# fpga_ram_V1.net
KiCad netlist of a schematic drawn in Altium Designer
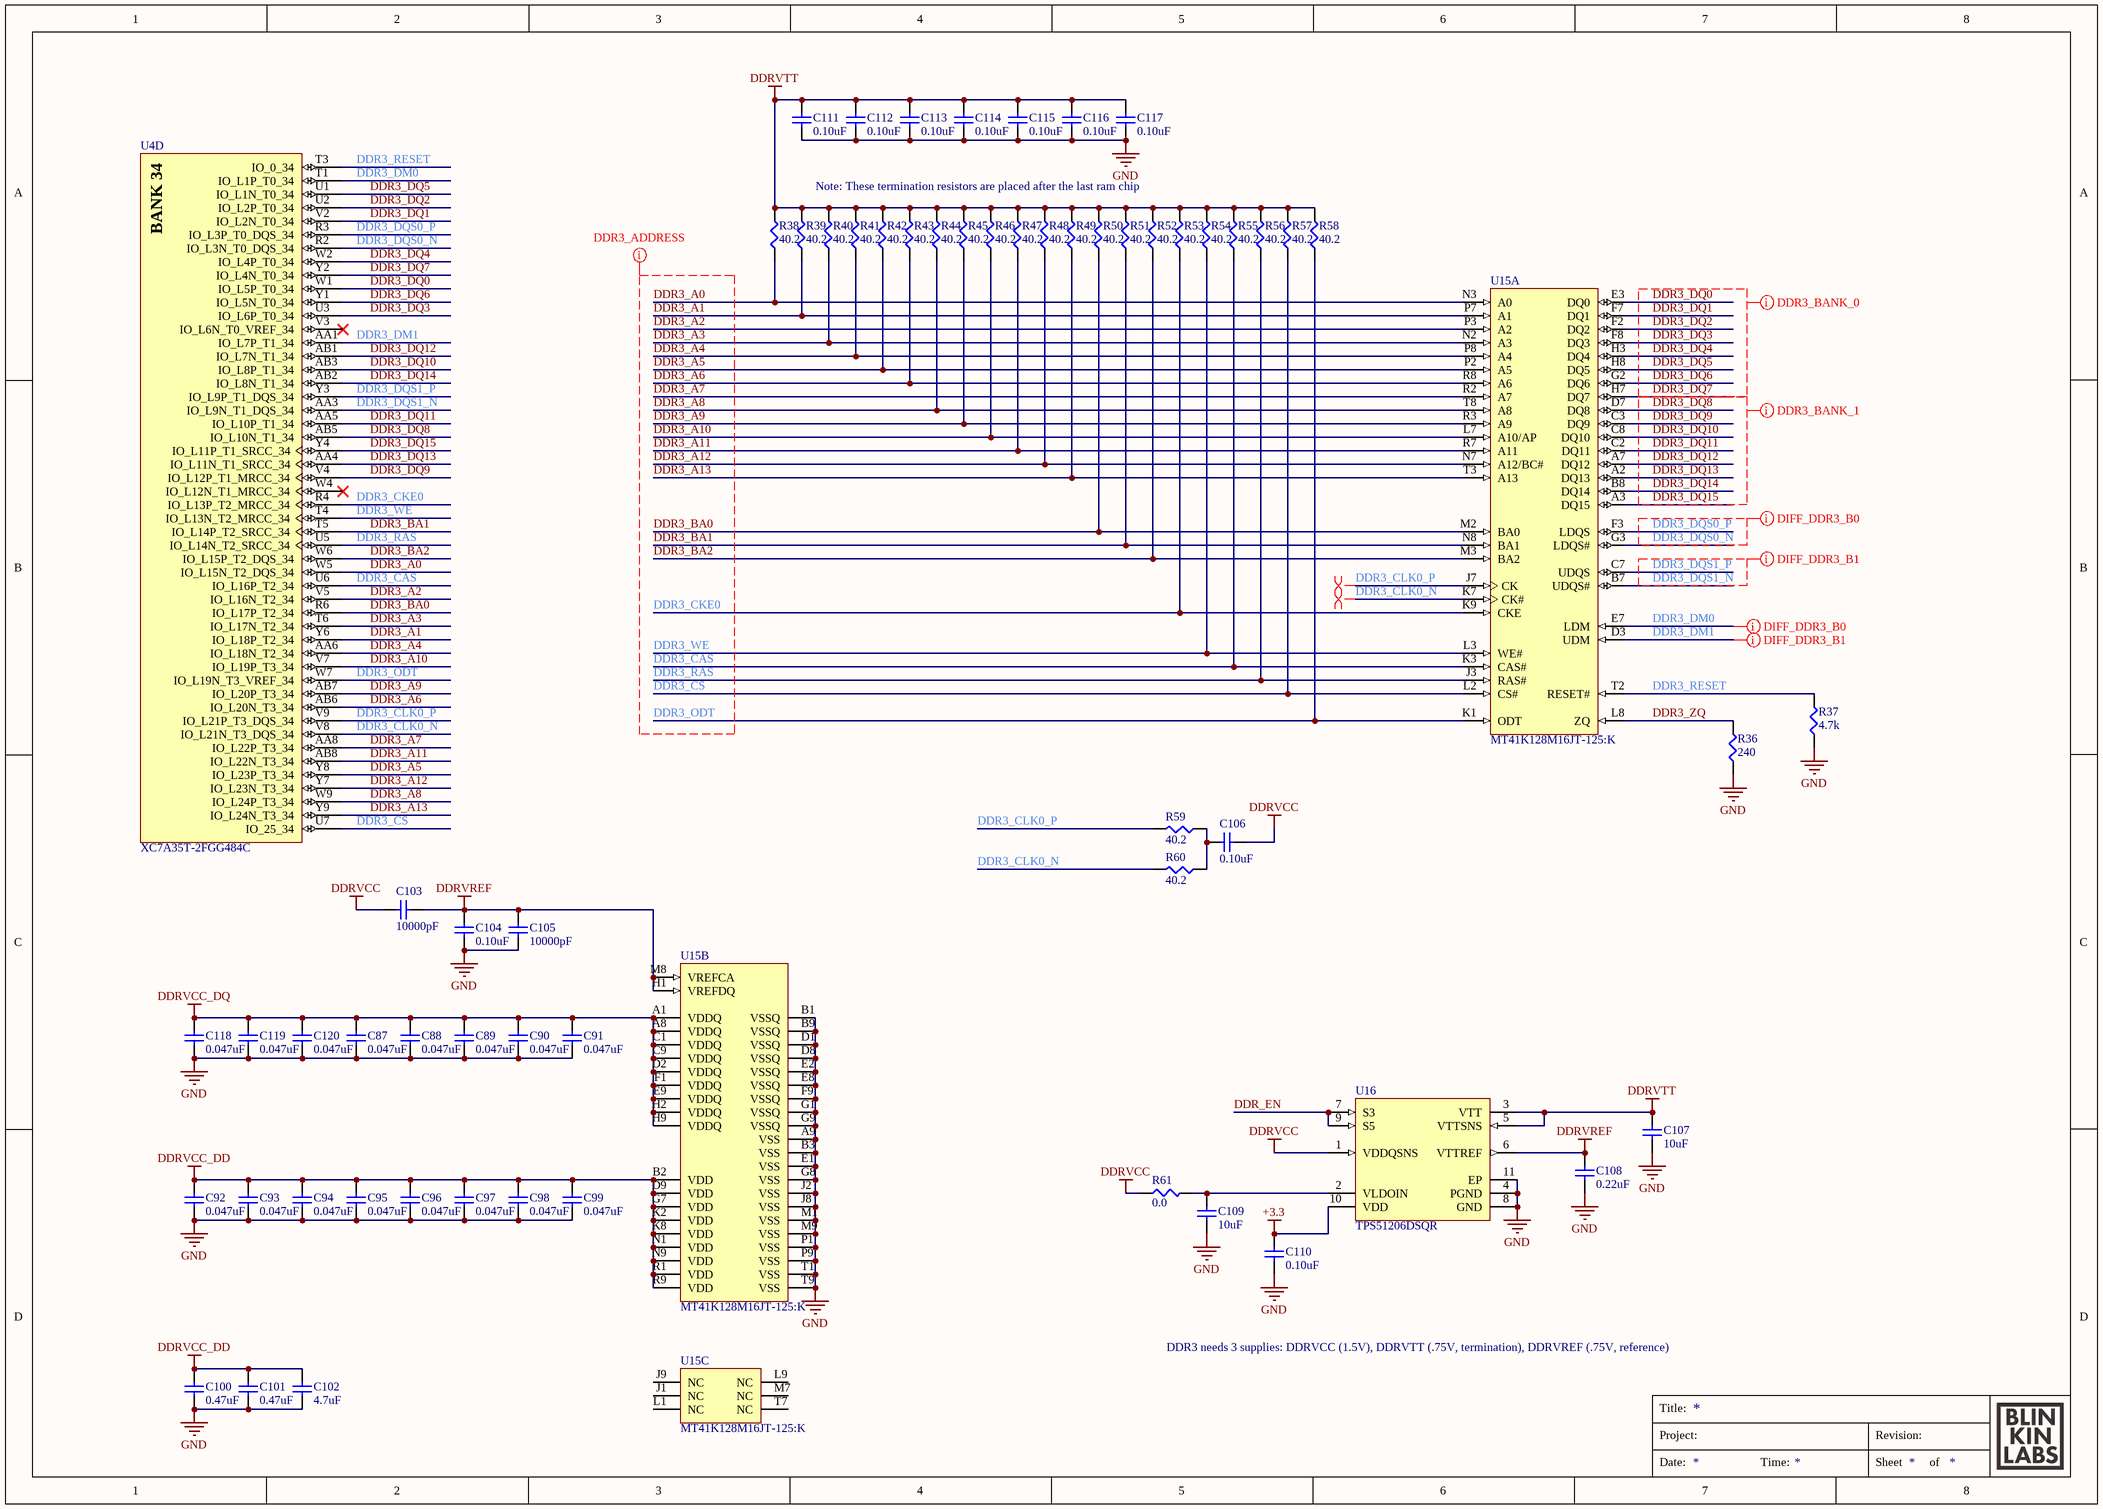
[diagram p0: fpga ram V1.SchDoc]

(export (version "E")
  (design (tool "Eeschema 10.0.6"))
  (components
    (comp (ref "C87")
      (value "0.047uF")
      (footprint "CAPC1005X06L")
      (description "CAP CER 0.047UF 6.3V X5R 0402")
      (fields
        (field (name "PARTNUMBER") "GRM155R60J473KA01D")
        (field (name "DIGI-KEY PART NUMBER") "490-8250-1-ND")
      )
      (libsource (lib "cap_murata") (part "CAPACITOR"))
    )
    (comp (ref "C88")
      (value "0.047uF")
      (footprint "CAPC1005X06L")
      (description "CAP CER 0.047UF 6.3V X5R 0402")
      (fields
        (field (name "PARTNUMBER") "GRM155R60J473KA01D")
        (field (name "DIGI-KEY PART NUMBER") "490-8250-1-ND")
      )
      (libsource (lib "cap_murata") (part "CAPACITOR"))
    )
    (comp (ref "C89")
      (value "0.047uF")
      (footprint "CAPC1005X06L")
      (description "CAP CER 0.047UF 6.3V X5R 0402")
      (fields
        (field (name "PARTNUMBER") "GRM155R60J473KA01D")
        (field (name "DIGI-KEY PART NUMBER") "490-8250-1-ND")
      )
      (libsource (lib "cap_murata") (part "CAPACITOR"))
    )
    (comp (ref "C90")
      (value "0.047uF")
      (footprint "CAPC1005X06L")
      (description "CAP CER 0.047UF 6.3V X5R 0402")
      (fields
        (field (name "PARTNUMBER") "GRM155R60J473KA01D")
        (field (name "DIGI-KEY PART NUMBER") "490-8250-1-ND")
      )
      (libsource (lib "cap_murata") (part "CAPACITOR"))
    )
    (comp (ref "C91")
      (value "0.047uF")
      (footprint "CAPC1005X06L")
      (description "CAP CER 0.047UF 6.3V X5R 0402")
      (fields
        (field (name "PARTNUMBER") "GRM155R60J473KA01D")
        (field (name "DIGI-KEY PART NUMBER") "490-8250-1-ND")
      )
      (libsource (lib "cap_murata") (part "CAPACITOR"))
    )
    (comp (ref "C92")
      (value "0.047uF")
      (footprint "CAPC1005X06L")
      (description "CAP CER 0.047UF 6.3V X5R 0402")
      (fields
        (field (name "PARTNUMBER") "GRM155R60J473KA01D")
        (field (name "DIGI-KEY PART NUMBER") "490-8250-1-ND")
      )
      (libsource (lib "cap_murata") (part "CAPACITOR"))
    )
    (comp (ref "C93")
      (value "0.047uF")
      (footprint "CAPC1005X06L")
      (description "CAP CER 0.047UF 6.3V X5R 0402")
      (fields
        (field (name "PARTNUMBER") "GRM155R60J473KA01D")
        (field (name "DIGI-KEY PART NUMBER") "490-8250-1-ND")
      )
      (libsource (lib "cap_murata") (part "CAPACITOR"))
    )
    (comp (ref "C94")
      (value "0.047uF")
      (footprint "CAPC1005X06L")
      (description "CAP CER 0.047UF 6.3V X5R 0402")
      (fields
        (field (name "PARTNUMBER") "GRM155R60J473KA01D")
        (field (name "DIGI-KEY PART NUMBER") "490-8250-1-ND")
      )
      (libsource (lib "cap_murata") (part "CAPACITOR"))
    )
    (comp (ref "C95")
      (value "0.047uF")
      (footprint "CAPC1005X06L")
      (description "CAP CER 0.047UF 6.3V X5R 0402")
      (fields
        (field (name "PARTNUMBER") "GRM155R60J473KA01D")
        (field (name "DIGI-KEY PART NUMBER") "490-8250-1-ND")
      )
      (libsource (lib "cap_murata") (part "CAPACITOR"))
    )
    (comp (ref "C96")
      (value "0.047uF")
      (footprint "CAPC1005X06L")
      (description "CAP CER 0.047UF 6.3V X5R 0402")
      (fields
        (field (name "PARTNUMBER") "GRM155R60J473KA01D")
        (field (name "DIGI-KEY PART NUMBER") "490-8250-1-ND")
      )
      (libsource (lib "cap_murata") (part "CAPACITOR"))
    )
    (comp (ref "C97")
      (value "0.047uF")
      (footprint "CAPC1005X06L")
      (description "CAP CER 0.047UF 6.3V X5R 0402")
      (fields
        (field (name "PARTNUMBER") "GRM155R60J473KA01D")
        (field (name "DIGI-KEY PART NUMBER") "490-8250-1-ND")
      )
      (libsource (lib "cap_murata") (part "CAPACITOR"))
    )
    (comp (ref "C98")
      (value "0.047uF")
      (footprint "CAPC1005X06L")
      (description "CAP CER 0.047UF 6.3V X5R 0402")
      (fields
        (field (name "PARTNUMBER") "GRM155R60J473KA01D")
        (field (name "DIGI-KEY PART NUMBER") "490-8250-1-ND")
      )
      (libsource (lib "cap_murata") (part "CAPACITOR"))
    )
    (comp (ref "C99")
      (value "0.047uF")
      (footprint "CAPC1005X06L")
      (description "CAP CER 0.047UF 6.3V X5R 0402")
      (fields
        (field (name "PARTNUMBER") "GRM155R60J473KA01D")
        (field (name "DIGI-KEY PART NUMBER") "490-8250-1-ND")
      )
      (libsource (lib "cap_murata") (part "CAPACITOR"))
    )
    (comp (ref "C100")
      (value "0.47uF")
      (footprint "CAPC1005X06L")
      (description "CAP CER 0.47UF 6.3V X5R 0402")
      (fields
        (field (name "PARTNUMBER") "GRM155R60J474KE19D")
        (field (name "DIGI-KEY PART NUMBER") "490-3266-1-ND")
      )
      (libsource (lib "cap_murata") (part "CAPACITOR"))
    )
    (comp (ref "C101")
      (value "0.47uF")
      (footprint "CAPC1005X06L")
      (description "CAP CER 0.47UF 6.3V X5R 0402")
      (fields
        (field (name "PARTNUMBER") "GRM155R60J474KE19D")
        (field (name "DIGI-KEY PART NUMBER") "490-3266-1-ND")
      )
      (libsource (lib "cap_murata") (part "CAPACITOR"))
    )
    (comp (ref "C102")
      (value "4.7uF")
      (footprint "CAPC1005X06L")
      (description "CAP CER 4.7UF 4V X5R 0402")
      (fields
        (field (name "PARTNUMBER") "GRM155R60G475ME47D")
        (field (name "DIGI-KEY PART NUMBER") "490-11980-1-ND")
      )
      (libsource (lib "cap_murata") (part "CAPACITOR"))
    )
    (comp (ref "C103")
      (value "10000pF")
      (footprint "CAPC1005X06L")
      (description "CAP CER 10000PF 16V X7R 0402")
      (fields
        (field (name "PARTNUMBER") "GRM155R71C103KA01D")
        (field (name "DIGI-KEY PART NUMBER") "490-1313-1-ND")
      )
      (libsource (lib "cap_murata") (part "CAPACITOR"))
    )
    (comp (ref "C104")
      (value "0.10uF")
      (footprint "CAPC1005X06L")
      (description "CAP CER 0.1UF 10V X5R 0402")
      (fields
        (field (name "PARTNUMBER") "GRM155R61A104KA01D")
        (field (name "DIGI-KEY PART NUMBER") "490-1318-1-ND")
      )
      (libsource (lib "cap_murata") (part "CAPACITOR"))
    )
    (comp (ref "C105")
      (value "10000pF")
      (footprint "CAPC1005X06L")
      (description "CAP CER 10000PF 16V X7R 0402")
      (fields
        (field (name "PARTNUMBER") "GRM155R71C103KA01D")
        (field (name "DIGI-KEY PART NUMBER") "490-1313-1-ND")
      )
      (libsource (lib "cap_murata") (part "CAPACITOR"))
    )
    (comp (ref "C106")
      (value "0.10uF")
      (footprint "CAPC1005X06L")
      (description "CAP CER 0.1UF 10V X5R 0402")
      (fields
        (field (name "PARTNUMBER") "GRM155R61A104KA01D")
        (field (name "DIGI-KEY PART NUMBER") "490-1318-1-ND")
      )
      (libsource (lib "cap_murata") (part "CAPACITOR"))
    )
    (comp (ref "C107")
      (value "10uF")
      (footprint "CAPC1608X09L")
      (description "CAP CER 10UF 6.3V X5R 0603")
      (fields
        (field (name "PARTNUMBER") "GRM188R60J106ME47D")
        (field (name "DIGI-KEY PART NUMBER") "490-3896-1-ND")
      )
      (libsource (lib "cap_murata") (part "CAPACITOR"))
    )
    (comp (ref "C108")
      (value "0.22uF")
      (footprint "CAPC1005X06L")
      (description "CAP CER 0.22UF 10V X5R 0402")
      (fields
        (field (name "PARTNUMBER") "GRM155R61A224KE19J")
        (field (name "DIGI-KEY PART NUMBER") "490-6303-1-ND")
      )
      (libsource (lib "cap_murata") (part "CAPACITOR"))
    )
    (comp (ref "C109")
      (value "10uF")
      (footprint "CAPC1608X09L")
      (description "CAP CER 10UF 6.3V X5R 0603")
      (fields
        (field (name "PARTNUMBER") "GRM188R60J106ME47D")
        (field (name "DIGI-KEY PART NUMBER") "490-3896-1-ND")
      )
      (libsource (lib "cap_murata") (part "CAPACITOR"))
    )
    (comp (ref "C110")
      (value "0.10uF")
      (footprint "CAPC1005X06L")
      (description "CAP CER 0.1UF 10V X5R 0402")
      (fields
        (field (name "PARTNUMBER") "GRM155R61A104KA01D")
        (field (name "DIGI-KEY PART NUMBER") "490-1318-1-ND")
      )
      (libsource (lib "cap_murata") (part "CAPACITOR"))
    )
    (comp (ref "C111")
      (value "0.10uF")
      (footprint "CAPC1005X06L")
      (description "CAP CER 0.1UF 10V X5R 0402")
      (fields
        (field (name "PARTNUMBER") "GRM155R61A104KA01D")
        (field (name "DIGI-KEY PART NUMBER") "490-1318-1-ND")
      )
      (libsource (lib "cap_murata") (part "CAPACITOR"))
    )
    (comp (ref "C112")
      (value "0.10uF")
      (footprint "CAPC1005X06L")
      (description "CAP CER 0.1UF 10V X5R 0402")
      (fields
        (field (name "PARTNUMBER") "GRM155R61A104KA01D")
        (field (name "DIGI-KEY PART NUMBER") "490-1318-1-ND")
      )
      (libsource (lib "cap_murata") (part "CAPACITOR"))
    )
    (comp (ref "C113")
      (value "0.10uF")
      (footprint "CAPC1005X06L")
      (description "CAP CER 0.1UF 10V X5R 0402")
      (fields
        (field (name "PARTNUMBER") "GRM155R61A104KA01D")
        (field (name "DIGI-KEY PART NUMBER") "490-1318-1-ND")
      )
      (libsource (lib "cap_murata") (part "CAPACITOR"))
    )
    (comp (ref "C114")
      (value "0.10uF")
      (footprint "CAPC1005X06L")
      (description "CAP CER 0.1UF 10V X5R 0402")
      (fields
        (field (name "PARTNUMBER") "GRM155R61A104KA01D")
        (field (name "DIGI-KEY PART NUMBER") "490-1318-1-ND")
      )
      (libsource (lib "cap_murata") (part "CAPACITOR"))
    )
    (comp (ref "C115")
      (value "0.10uF")
      (footprint "CAPC1005X06L")
      (description "CAP CER 0.1UF 10V X5R 0402")
      (fields
        (field (name "PARTNUMBER") "GRM155R61A104KA01D")
        (field (name "DIGI-KEY PART NUMBER") "490-1318-1-ND")
      )
      (libsource (lib "cap_murata") (part "CAPACITOR"))
    )
    (comp (ref "C116")
      (value "0.10uF")
      (footprint "CAPC1005X06L")
      (description "CAP CER 0.1UF 10V X5R 0402")
      (fields
        (field (name "PARTNUMBER") "GRM155R61A104KA01D")
        (field (name "DIGI-KEY PART NUMBER") "490-1318-1-ND")
      )
      (libsource (lib "cap_murata") (part "CAPACITOR"))
    )
    (comp (ref "C117")
      (value "0.10uF")
      (footprint "CAPC1005X06L")
      (description "CAP CER 0.1UF 10V X5R 0402")
      (fields
        (field (name "PARTNUMBER") "GRM155R61A104KA01D")
        (field (name "DIGI-KEY PART NUMBER") "490-1318-1-ND")
      )
      (libsource (lib "cap_murata") (part "CAPACITOR"))
    )
    (comp (ref "C118")
      (value "0.047uF")
      (footprint "CAPC1005X06L")
      (description "CAP CER 0.047UF 6.3V X5R 0402")
      (fields
        (field (name "PARTNUMBER") "GRM155R60J473KA01D")
        (field (name "DIGI-KEY PART NUMBER") "490-8250-1-ND")
      )
      (libsource (lib "cap_murata") (part "CAPACITOR"))
    )
    (comp (ref "C119")
      (value "0.047uF")
      (footprint "CAPC1005X06L")
      (description "CAP CER 0.047UF 6.3V X5R 0402")
      (fields
        (field (name "PARTNUMBER") "GRM155R60J473KA01D")
        (field (name "DIGI-KEY PART NUMBER") "490-8250-1-ND")
      )
      (libsource (lib "cap_murata") (part "CAPACITOR"))
    )
    (comp (ref "C120")
      (value "0.047uF")
      (footprint "CAPC1005X06L")
      (description "CAP CER 0.047UF 6.3V X5R 0402")
      (fields
        (field (name "PARTNUMBER") "GRM155R60J473KA01D")
        (field (name "DIGI-KEY PART NUMBER") "490-8250-1-ND")
      )
      (libsource (lib "cap_murata") (part "CAPACITOR"))
    )
    (comp (ref "R36")
      (value "240")
      (footprint "ERJ2G(0402)_L")
      (description "RES SMD 240 OHM 1% 1/10W 0402")
      (fields (field (name "PARTNUMBER") "ERJ-2RKF2400X") (field (name "DIGI-KEY PART NUMBER") "P240LCT-ND"))
      (libsource (lib "res_panasonic_erj_xls") (part "RESISTOR"))
    )
    (comp (ref "R37")
      (value "4.7k")
      (footprint "ERJ2G(0402)_L")
      (description "RES SMD 4.7K OHM 1% 1/5W 0402")
      (fields (field (name "PARTNUMBER") "ERJ-PA2F4701X") (field (name "DIGI-KEY PART NUMBER") "P17228CT-ND"))
      (libsource (lib "res_panasonic_erj_xls") (part "RESISTOR"))
    )
    (comp (ref "R38")
      (value "40.2")
      (footprint "ERJ2G(0402)_L")
      (description "RES SMD 40.2 OHM 1% 1/10W 0402")
      (fields (field (name "PARTNUMBER") "ERJ-2RKF40R2X") (field (name "DIGI-KEY PART NUMBER") "P40.2LCT-ND"))
      (libsource (lib "res_panasonic_erj_xls") (part "RESISTOR"))
    )
    (comp (ref "R39")
      (value "40.2")
      (footprint "ERJ2G(0402)_L")
      (description "RES SMD 40.2 OHM 1% 1/10W 0402")
      (fields (field (name "PARTNUMBER") "ERJ-2RKF40R2X") (field (name "DIGI-KEY PART NUMBER") "P40.2LCT-ND"))
      (libsource (lib "res_panasonic_erj_xls") (part "RESISTOR"))
    )
    (comp (ref "R40")
      (value "40.2")
      (footprint "ERJ2G(0402)_L")
      (description "RES SMD 40.2 OHM 1% 1/10W 0402")
      (fields (field (name "PARTNUMBER") "ERJ-2RKF40R2X") (field (name "DIGI-KEY PART NUMBER") "P40.2LCT-ND"))
      (libsource (lib "res_panasonic_erj_xls") (part "RESISTOR"))
    )
    (comp (ref "R41")
      (value "40.2")
      (footprint "ERJ2G(0402)_L")
      (description "RES SMD 40.2 OHM 1% 1/10W 0402")
      (fields (field (name "PARTNUMBER") "ERJ-2RKF40R2X") (field (name "DIGI-KEY PART NUMBER") "P40.2LCT-ND"))
      (libsource (lib "res_panasonic_erj_xls") (part "RESISTOR"))
    )
    (comp (ref "R42")
      (value "40.2")
      (footprint "ERJ2G(0402)_L")
      (description "RES SMD 40.2 OHM 1% 1/10W 0402")
      (fields (field (name "PARTNUMBER") "ERJ-2RKF40R2X") (field (name "DIGI-KEY PART NUMBER") "P40.2LCT-ND"))
      (libsource (lib "res_panasonic_erj_xls") (part "RESISTOR"))
    )
    (comp (ref "R43")
      (value "40.2")
      (footprint "ERJ2G(0402)_L")
      (description "RES SMD 40.2 OHM 1% 1/10W 0402")
      (fields (field (name "PARTNUMBER") "ERJ-2RKF40R2X") (field (name "DIGI-KEY PART NUMBER") "P40.2LCT-ND"))
      (libsource (lib "res_panasonic_erj_xls") (part "RESISTOR"))
    )
    (comp (ref "R44")
      (value "40.2")
      (footprint "ERJ2G(0402)_L")
      (description "RES SMD 40.2 OHM 1% 1/10W 0402")
      (fields (field (name "PARTNUMBER") "ERJ-2RKF40R2X") (field (name "DIGI-KEY PART NUMBER") "P40.2LCT-ND"))
      (libsource (lib "res_panasonic_erj_xls") (part "RESISTOR"))
    )
    (comp (ref "R45")
      (value "40.2")
      (footprint "ERJ2G(0402)_L")
      (description "RES SMD 40.2 OHM 1% 1/10W 0402")
      (fields (field (name "PARTNUMBER") "ERJ-2RKF40R2X") (field (name "DIGI-KEY PART NUMBER") "P40.2LCT-ND"))
      (libsource (lib "res_panasonic_erj_xls") (part "RESISTOR"))
    )
    (comp (ref "R46")
      (value "40.2")
      (footprint "ERJ2G(0402)_L")
      (description "RES SMD 40.2 OHM 1% 1/10W 0402")
      (fields (field (name "PARTNUMBER") "ERJ-2RKF40R2X") (field (name "DIGI-KEY PART NUMBER") "P40.2LCT-ND"))
      (libsource (lib "res_panasonic_erj_xls") (part "RESISTOR"))
    )
    (comp (ref "R47")
      (value "40.2")
      (footprint "ERJ2G(0402)_L")
      (description "RES SMD 40.2 OHM 1% 1/10W 0402")
      (fields (field (name "PARTNUMBER") "ERJ-2RKF40R2X") (field (name "DIGI-KEY PART NUMBER") "P40.2LCT-ND"))
      (libsource (lib "res_panasonic_erj_xls") (part "RESISTOR"))
    )
    (comp (ref "R48")
      (value "40.2")
      (footprint "ERJ2G(0402)_L")
      (description "RES SMD 40.2 OHM 1% 1/10W 0402")
      (fields (field (name "PARTNUMBER") "ERJ-2RKF40R2X") (field (name "DIGI-KEY PART NUMBER") "P40.2LCT-ND"))
      (libsource (lib "res_panasonic_erj_xls") (part "RESISTOR"))
    )
    (comp (ref "R49")
      (value "40.2")
      (footprint "ERJ2G(0402)_L")
      (description "RES SMD 40.2 OHM 1% 1/10W 0402")
      (fields (field (name "PARTNUMBER") "ERJ-2RKF40R2X") (field (name "DIGI-KEY PART NUMBER") "P40.2LCT-ND"))
      (libsource (lib "res_panasonic_erj_xls") (part "RESISTOR"))
    )
    (comp (ref "R50")
      (value "40.2")
      (footprint "ERJ2G(0402)_L")
      (description "RES SMD 40.2 OHM 1% 1/10W 0402")
      (fields (field (name "PARTNUMBER") "ERJ-2RKF40R2X") (field (name "DIGI-KEY PART NUMBER") "P40.2LCT-ND"))
      (libsource (lib "res_panasonic_erj_xls") (part "RESISTOR"))
    )
    (comp (ref "R51")
      (value "40.2")
      (footprint "ERJ2G(0402)_L")
      (description "RES SMD 40.2 OHM 1% 1/10W 0402")
      (fields (field (name "PARTNUMBER") "ERJ-2RKF40R2X") (field (name "DIGI-KEY PART NUMBER") "P40.2LCT-ND"))
      (libsource (lib "res_panasonic_erj_xls") (part "RESISTOR"))
    )
    (comp (ref "R52")
      (value "40.2")
      (footprint "ERJ2G(0402)_L")
      (description "RES SMD 40.2 OHM 1% 1/10W 0402")
      (fields (field (name "PARTNUMBER") "ERJ-2RKF40R2X") (field (name "DIGI-KEY PART NUMBER") "P40.2LCT-ND"))
      (libsource (lib "res_panasonic_erj_xls") (part "RESISTOR"))
    )
    (comp (ref "R53")
      (value "40.2")
      (footprint "ERJ2G(0402)_L")
      (description "RES SMD 40.2 OHM 1% 1/10W 0402")
      (fields (field (name "PARTNUMBER") "ERJ-2RKF40R2X") (field (name "DIGI-KEY PART NUMBER") "P40.2LCT-ND"))
      (libsource (lib "res_panasonic_erj_xls") (part "RESISTOR"))
    )
    (comp (ref "R54")
      (value "40.2")
      (footprint "ERJ2G(0402)_L")
      (description "RES SMD 40.2 OHM 1% 1/10W 0402")
      (fields (field (name "PARTNUMBER") "ERJ-2RKF40R2X") (field (name "DIGI-KEY PART NUMBER") "P40.2LCT-ND"))
      (libsource (lib "res_panasonic_erj_xls") (part "RESISTOR"))
    )
    (comp (ref "R55")
      (value "40.2")
      (footprint "ERJ2G(0402)_L")
      (description "RES SMD 40.2 OHM 1% 1/10W 0402")
      (fields (field (name "PARTNUMBER") "ERJ-2RKF40R2X") (field (name "DIGI-KEY PART NUMBER") "P40.2LCT-ND"))
      (libsource (lib "res_panasonic_erj_xls") (part "RESISTOR"))
    )
    (comp (ref "R56")
      (value "40.2")
      (footprint "ERJ2G(0402)_L")
      (description "RES SMD 40.2 OHM 1% 1/10W 0402")
      (fields (field (name "PARTNUMBER") "ERJ-2RKF40R2X") (field (name "DIGI-KEY PART NUMBER") "P40.2LCT-ND"))
      (libsource (lib "res_panasonic_erj_xls") (part "RESISTOR"))
    )
    (comp (ref "R57")
      (value "40.2")
      (footprint "ERJ2G(0402)_L")
      (description "RES SMD 40.2 OHM 1% 1/10W 0402")
      (fields (field (name "PARTNUMBER") "ERJ-2RKF40R2X") (field (name "DIGI-KEY PART NUMBER") "P40.2LCT-ND"))
      (libsource (lib "res_panasonic_erj_xls") (part "RESISTOR"))
    )
    (comp (ref "R58")
      (value "40.2")
      (footprint "ERJ2G(0402)_L")
      (description "RES SMD 40.2 OHM 1% 1/10W 0402")
      (fields (field (name "PARTNUMBER") "ERJ-2RKF40R2X") (field (name "DIGI-KEY PART NUMBER") "P40.2LCT-ND"))
      (libsource (lib "res_panasonic_erj_xls") (part "RESISTOR"))
    )
    (comp (ref "R59")
      (value "40.2")
      (footprint "ERJ2G(0402)_L")
      (description "RES SMD 40.2 OHM 1% 1/10W 0402")
      (fields (field (name "PARTNUMBER") "ERJ-2RKF40R2X") (field (name "DIGI-KEY PART NUMBER") "P40.2LCT-ND"))
      (libsource (lib "res_panasonic_erj_xls") (part "RESISTOR"))
    )
    (comp (ref "R60")
      (value "40.2")
      (footprint "ERJ2G(0402)_L")
      (description "RES SMD 40.2 OHM 1% 1/10W 0402")
      (fields (field (name "PARTNUMBER") "ERJ-2RKF40R2X") (field (name "DIGI-KEY PART NUMBER") "P40.2LCT-ND"))
      (libsource (lib "res_panasonic_erj_xls") (part "RESISTOR"))
    )
    (comp (ref "R61")
      (value "0.0")
      (footprint "ERJ3G(0603)_L")
      (description "RES SMD 0.0OHM JUMPER 1/10W 0603")
      (fields (field (name "PARTNUMBER") "ERJ-3GEY0R00V") (field (name "DIGI-KEY PART NUMBER") "P0.0GCT-ND"))
      (libsource (lib "res_panasonic_erj_xls") (part "RESISTOR"))
    )
    (comp (ref "U4")
      (value "XC7A35T-2FGG484C")
      (footprint "FGG484")
      (description "Artix-7 FPGA, 250 User I/Os, 4 GTP, 484-Ball BGA, Speed Grade 2, Commercial Grade, Pb-Free")
      (fields (field (name "MANUFACTURER") "Xilinx"))
      (libsource (lib "Altium Content Vault") (part "XLNX-XC7A35T-FGG484"))
    )
    (comp (ref "U15")
      (value "MT41K128M16JT-125:K")
      (footprint "MICT-JT-96")
      (description "2Gb DDR3-1600 SDRAM, 128Mb x 16, 1.25 ns, 1.35 V, 0 to 95 degC, 96-Ball FBGA")
      (fields (field (name "MANUFACTURER") "Micron"))
      (libsource (lib "Altium Content Vault") (part "MICT-MT41K128M16JT-96"))
    )
    (comp (ref "U16")
      (value "TPS51206DSQR")
      (footprint "DSQ0010A_V")
      (fields (field (name "MANUFACTURER") "Texas Instruments"))
      (libsource (lib "Altium Content Vault") (part "TI-TPS51206DSQ10-1500X900TP"))
    )
  )
  (nets
    (net (code "1") (name "+3.3") (class "Default")
      (node (ref "C110") (pin "1") (pinfunction "1_1") (pintype "passive"))
      (node (ref "U16") (pin "10") (pinfunction "VDD_10") (pintype "power_in"))
    )
    (net (code "2") (name "/DDR3_A0") (class "Default")
      (node (ref "R38") (pin "1") (pinfunction "1_1") (pintype "passive"))
      (node (ref "U15") (pin "N3") (pinfunction "A0_N3") (pintype "input"))
      (node (ref "U4") (pin "W5") (pinfunction "IO_L15N_T2_DQS_34_W5") (pintype "bidirectional"))
    )
    (net (code "3") (name "/DDR3_A1") (class "Default")
      (node (ref "R39") (pin "1") (pinfunction "1_1") (pintype "passive"))
      (node (ref "U15") (pin "P7") (pinfunction "A1_P7") (pintype "input"))
      (node (ref "U4") (pin "Y6") (pinfunction "IO_L18P_T2_34_Y6") (pintype "bidirectional"))
    )
    (net (code "4") (name "/DDR3_A2") (class "Default")
      (node (ref "U15") (pin "P3") (pinfunction "A2_P3") (pintype "input"))
      (node (ref "U4") (pin "V5") (pinfunction "IO_L16N_T2_34_V5") (pintype "bidirectional"))
    )
    (net (code "5") (name "/DDR3_A3") (class "Default")
      (node (ref "R40") (pin "1") (pinfunction "1_1") (pintype "passive"))
      (node (ref "U15") (pin "N2") (pinfunction "A3_N2") (pintype "input"))
      (node (ref "U4") (pin "T6") (pinfunction "IO_L17N_T2_34_T6") (pintype "bidirectional"))
    )
    (net (code "6") (name "/DDR3_A4") (class "Default")
      (node (ref "R41") (pin "1") (pinfunction "1_1") (pintype "passive"))
      (node (ref "U15") (pin "P8") (pinfunction "A4_P8") (pintype "input"))
      (node (ref "U4") (pin "AA6") (pinfunction "IO_L18N_T2_34_AA6") (pintype "bidirectional"))
    )
    (net (code "7") (name "/DDR3_A5") (class "Default")
      (node (ref "R42") (pin "1") (pinfunction "1_1") (pintype "passive"))
      (node (ref "U15") (pin "P2") (pinfunction "A5_P2") (pintype "input"))
      (node (ref "U4") (pin "Y8") (pinfunction "IO_L23P_T3_34_Y8") (pintype "bidirectional"))
    )
    (net (code "8") (name "/DDR3_A6") (class "Default")
      (node (ref "R43") (pin "1") (pinfunction "1_1") (pintype "passive"))
      (node (ref "U15") (pin "R8") (pinfunction "A6_R8") (pintype "input"))
      (node (ref "U4") (pin "AB6") (pinfunction "IO_L20N_T3_34_AB6") (pintype "bidirectional"))
    )
    (net (code "9") (name "/DDR3_A7") (class "Default")
      (node (ref "U15") (pin "R2") (pinfunction "A7_R2") (pintype "input"))
      (node (ref "U4") (pin "AA8") (pinfunction "IO_L22P_T3_34_AA8") (pintype "bidirectional"))
    )
    (net (code "10") (name "/DDR3_A8") (class "Default")
      (node (ref "R44") (pin "1") (pinfunction "1_1") (pintype "passive"))
      (node (ref "U15") (pin "T8") (pinfunction "A8_T8") (pintype "input"))
      (node (ref "U4") (pin "W9") (pinfunction "IO_L24P_T3_34_W9") (pintype "bidirectional"))
    )
    (net (code "11") (name "/DDR3_A9") (class "Default")
      (node (ref "R45") (pin "1") (pinfunction "1_1") (pintype "passive"))
      (node (ref "U15") (pin "R3") (pinfunction "A9_R3") (pintype "input"))
      (node (ref "U4") (pin "AB7") (pinfunction "IO_L20P_T3_34_AB7") (pintype "bidirectional"))
    )
    (net (code "12") (name "/DDR3_A10") (class "Default")
      (node (ref "R46") (pin "1") (pinfunction "1_1") (pintype "passive"))
      (node (ref "U15") (pin "L7") (pinfunction "A10/AP_L7") (pintype "input"))
      (node (ref "U4") (pin "V7") (pinfunction "IO_L19P_T3_34_V7") (pintype "bidirectional"))
    )
    (net (code "13") (name "/DDR3_A11") (class "Default")
      (node (ref "R47") (pin "1") (pinfunction "1_1") (pintype "passive"))
      (node (ref "U15") (pin "R7") (pinfunction "A11_R7") (pintype "input"))
      (node (ref "U4") (pin "AB8") (pinfunction "IO_L22N_T3_34_AB8") (pintype "bidirectional"))
    )
    (net (code "14") (name "/DDR3_A12") (class "Default")
      (node (ref "R48") (pin "1") (pinfunction "1_1") (pintype "passive"))
      (node (ref "U15") (pin "N7") (pinfunction "A12/BC#_N7") (pintype "input"))
      (node (ref "U4") (pin "Y7") (pinfunction "IO_L23N_T3_34_Y7") (pintype "bidirectional"))
    )
    (net (code "15") (name "/DDR3_A13") (class "Default")
      (node (ref "R49") (pin "1") (pinfunction "1_1") (pintype "passive"))
      (node (ref "U15") (pin "T3") (pinfunction "A13_T3") (pintype "input"))
      (node (ref "U4") (pin "Y9") (pinfunction "IO_L24N_T3_34_Y9") (pintype "bidirectional"))
    )
    (net (code "16") (name "/DDR3_BA0") (class "Default")
      (node (ref "R50") (pin "1") (pinfunction "1_1") (pintype "passive"))
      (node (ref "U15") (pin "M2") (pinfunction "BA0_M2") (pintype "input"))
      (node (ref "U4") (pin "R6") (pinfunction "IO_L17P_T2_34_R6") (pintype "bidirectional"))
    )
    (net (code "17") (name "/DDR3_BA1") (class "Default")
      (node (ref "R51") (pin "1") (pinfunction "1_1") (pintype "passive"))
      (node (ref "U15") (pin "N8") (pinfunction "BA1_N8") (pintype "input"))
      (node (ref "U4") (pin "T5") (pinfunction "IO_L14P_T2_SRCC_34_T5") (pintype "bidirectional"))
    )
    (net (code "18") (name "/DDR3_BA2") (class "Default")
      (node (ref "R52") (pin "1") (pinfunction "1_1") (pintype "passive"))
      (node (ref "U15") (pin "M3") (pinfunction "BA2_M3") (pintype "input"))
      (node (ref "U4") (pin "W6") (pinfunction "IO_L15P_T2_DQS_34_W6") (pintype "bidirectional"))
    )
    (net (code "19") (name "/DDR3_CAS") (class "Default")
      (node (ref "R55") (pin "1") (pinfunction "1_1") (pintype "passive"))
      (node (ref "U15") (pin "K3") (pinfunction "CAS#_K3") (pintype "input"))
      (node (ref "U4") (pin "U6") (pinfunction "IO_L16P_T2_34_U6") (pintype "bidirectional"))
    )
    (net (code "20") (name "/DDR3_CKE0") (class "Default")
      (node (ref "R53") (pin "1") (pinfunction "1_1") (pintype "passive"))
      (node (ref "U15") (pin "K9") (pinfunction "CKE_K9") (pintype "input"))
      (node (ref "U4") (pin "R4") (pinfunction "IO_L13P_T2_MRCC_34_R4") (pintype "bidirectional"))
    )
    (net (code "21") (name "/DDR3_CLK0_N") (class "Default")
      (node (ref "R60") (pin "2") (pinfunction "2_2") (pintype "passive"))
      (node (ref "U15") (pin "K7") (pinfunction "CK#_K7") (pintype "input"))
      (node (ref "U4") (pin "V8") (pinfunction "IO_L21N_T3_DQS_34_V8") (pintype "bidirectional"))
    )
    (net (code "22") (name "/DDR3_CLK0_P") (class "Default")
      (node (ref "R59") (pin "2") (pinfunction "2_2") (pintype "passive"))
      (node (ref "U15") (pin "J7") (pinfunction "CK_J7") (pintype "input"))
      (node (ref "U4") (pin "V9") (pinfunction "IO_L21P_T3_DQS_34_V9") (pintype "bidirectional"))
    )
    (net (code "23") (name "/DDR3_CS") (class "Default")
      (node (ref "R57") (pin "1") (pinfunction "1_1") (pintype "passive"))
      (node (ref "U15") (pin "L2") (pinfunction "CS#_L2") (pintype "input"))
      (node (ref "U4") (pin "U7") (pinfunction "IO_25_34_U7") (pintype "bidirectional"))
    )
    (net (code "24") (name "/DDR3_DM0") (class "Default")
      (node (ref "U15") (pin "E7") (pinfunction "LDM_E7") (pintype "input"))
      (node (ref "U4") (pin "T1") (pinfunction "IO_L1P_T0_34_T1") (pintype "bidirectional"))
    )
    (net (code "25") (name "/DDR3_DM1") (class "Default")
      (node (ref "U15") (pin "D3") (pinfunction "UDM_D3") (pintype "input"))
      (node (ref "U4") (pin "AA1") (pinfunction "IO_L7P_T1_34_AA1") (pintype "bidirectional"))
    )
    (net (code "26") (name "/DDR3_DQ0") (class "Default")
      (node (ref "U15") (pin "E3") (pinfunction "DQ0_E3") (pintype "bidirectional"))
      (node (ref "U4") (pin "W1") (pinfunction "IO_L5P_T0_34_W1") (pintype "bidirectional"))
    )
    (net (code "27") (name "/DDR3_DQ1") (class "Default")
      (node (ref "U15") (pin "F7") (pinfunction "DQ1_F7") (pintype "bidirectional"))
      (node (ref "U4") (pin "V2") (pinfunction "IO_L2N_T0_34_V2") (pintype "bidirectional"))
    )
    (net (code "28") (name "/DDR3_DQ2") (class "Default")
      (node (ref "U15") (pin "F2") (pinfunction "DQ2_F2") (pintype "bidirectional"))
      (node (ref "U4") (pin "U2") (pinfunction "IO_L2P_T0_34_U2") (pintype "bidirectional"))
    )
    (net (code "29") (name "/DDR3_DQ3") (class "Default")
      (node (ref "U15") (pin "F8") (pinfunction "DQ3_F8") (pintype "bidirectional"))
      (node (ref "U4") (pin "U3") (pinfunction "IO_L6P_T0_34_U3") (pintype "bidirectional"))
    )
    (net (code "30") (name "/DDR3_DQ4") (class "Default")
      (node (ref "U15") (pin "H3") (pinfunction "DQ4_H3") (pintype "bidirectional"))
      (node (ref "U4") (pin "W2") (pinfunction "IO_L4P_T0_34_W2") (pintype "bidirectional"))
    )
    (net (code "31") (name "/DDR3_DQ5") (class "Default")
      (node (ref "U15") (pin "H8") (pinfunction "DQ5_H8") (pintype "bidirectional"))
      (node (ref "U4") (pin "U1") (pinfunction "IO_L1N_T0_34_U1") (pintype "bidirectional"))
    )
    (net (code "32") (name "/DDR3_DQ6") (class "Default")
      (node (ref "U15") (pin "G2") (pinfunction "DQ6_G2") (pintype "bidirectional"))
      (node (ref "U4") (pin "Y1") (pinfunction "IO_L5N_T0_34_Y1") (pintype "bidirectional"))
    )
    (net (code "33") (name "/DDR3_DQ7") (class "Default")
      (node (ref "U15") (pin "H7") (pinfunction "DQ7_H7") (pintype "bidirectional"))
      (node (ref "U4") (pin "Y2") (pinfunction "IO_L4N_T0_34_Y2") (pintype "bidirectional"))
    )
    (net (code "34") (name "/DDR3_DQ8") (class "Default")
      (node (ref "U15") (pin "D7") (pinfunction "DQ8_D7") (pintype "bidirectional"))
      (node (ref "U4") (pin "AB5") (pinfunction "IO_L10N_T1_34_AB5") (pintype "bidirectional"))
    )
    (net (code "35") (name "/DDR3_DQ9") (class "Default")
      (node (ref "U15") (pin "C3") (pinfunction "DQ9_C3") (pintype "bidirectional"))
      (node (ref "U4") (pin "V4") (pinfunction "IO_L12P_T1_MRCC_34_V4") (pintype "bidirectional"))
    )
    (net (code "36") (name "/DDR3_DQ10") (class "Default")
      (node (ref "U15") (pin "C8") (pinfunction "DQ10_C8") (pintype "bidirectional"))
      (node (ref "U4") (pin "AB3") (pinfunction "IO_L8P_T1_34_AB3") (pintype "bidirectional"))
    )
    (net (code "37") (name "/DDR3_DQ11") (class "Default")
      (node (ref "U15") (pin "C2") (pinfunction "DQ11_C2") (pintype "bidirectional"))
      (node (ref "U4") (pin "AA5") (pinfunction "IO_L10P_T1_34_AA5") (pintype "bidirectional"))
    )
    (net (code "38") (name "/DDR3_DQ12") (class "Default")
      (node (ref "U15") (pin "A7") (pinfunction "DQ12_A7") (pintype "bidirectional"))
      (node (ref "U4") (pin "AB1") (pinfunction "IO_L7N_T1_34_AB1") (pintype "bidirectional"))
    )
    (net (code "39") (name "/DDR3_DQ13") (class "Default")
      (node (ref "U15") (pin "A2") (pinfunction "DQ13_A2") (pintype "bidirectional"))
      (node (ref "U4") (pin "AA4") (pinfunction "IO_L11N_T1_SRCC_34_AA4") (pintype "bidirectional"))
    )
    (net (code "40") (name "/DDR3_DQ14") (class "Default")
      (node (ref "U15") (pin "B8") (pinfunction "DQ14_B8") (pintype "bidirectional"))
      (node (ref "U4") (pin "AB2") (pinfunction "IO_L8N_T1_34_AB2") (pintype "bidirectional"))
    )
    (net (code "41") (name "/DDR3_DQ15") (class "Default")
      (node (ref "U15") (pin "A3") (pinfunction "DQ15_A3") (pintype "bidirectional"))
      (node (ref "U4") (pin "Y4") (pinfunction "IO_L11P_T1_SRCC_34_Y4") (pintype "bidirectional"))
    )
    (net (code "42") (name "/DDR3_DQS0_N") (class "Default")
      (node (ref "U15") (pin "G3") (pinfunction "LDQS#_G3") (pintype "bidirectional"))
      (node (ref "U4") (pin "R2") (pinfunction "IO_L3N_T0_DQS_34_R2") (pintype "bidirectional"))
    )
    (net (code "43") (name "/DDR3_DQS0_P") (class "Default")
      (node (ref "U15") (pin "F3") (pinfunction "LDQS_F3") (pintype "bidirectional"))
      (node (ref "U4") (pin "R3") (pinfunction "IO_L3P_T0_DQS_34_R3") (pintype "bidirectional"))
    )
    (net (code "44") (name "/DDR3_DQS1_N") (class "Default")
      (node (ref "U15") (pin "B7") (pinfunction "UDQS#_B7") (pintype "bidirectional"))
      (node (ref "U4") (pin "AA3") (pinfunction "IO_L9N_T1_DQS_34_AA3") (pintype "bidirectional"))
    )
    (net (code "45") (name "/DDR3_DQS1_P") (class "Default")
      (node (ref "U15") (pin "C7") (pinfunction "UDQS_C7") (pintype "bidirectional"))
      (node (ref "U4") (pin "Y3") (pinfunction "IO_L9P_T1_DQS_34_Y3") (pintype "bidirectional"))
    )
    (net (code "46") (name "/DDR3_ODT") (class "Default")
      (node (ref "R58") (pin "1") (pinfunction "1_1") (pintype "passive"))
      (node (ref "U15") (pin "K1") (pinfunction "ODT_K1") (pintype "input"))
      (node (ref "U4") (pin "W7") (pinfunction "IO_L19N_T3_VREF_34_W7") (pintype "bidirectional"))
    )
    (net (code "47") (name "/DDR3_RAS") (class "Default")
      (node (ref "R56") (pin "1") (pinfunction "1_1") (pintype "passive"))
      (node (ref "U15") (pin "J3") (pinfunction "RAS#_J3") (pintype "input"))
      (node (ref "U4") (pin "U5") (pinfunction "IO_L14N_T2_SRCC_34_U5") (pintype "bidirectional"))
    )
    (net (code "48") (name "/DDR3_RESET") (class "Default")
      (node (ref "R37") (pin "2") (pinfunction "2_2") (pintype "passive"))
      (node (ref "U15") (pin "T2") (pinfunction "RESET#_T2") (pintype "input"))
      (node (ref "U4") (pin "T3") (pinfunction "IO_0_34_T3") (pintype "bidirectional"))
    )
    (net (code "49") (name "/DDR3_WE") (class "Default")
      (node (ref "R54") (pin "1") (pinfunction "1_1") (pintype "passive"))
      (node (ref "U15") (pin "L3") (pinfunction "WE#_L3") (pintype "input"))
      (node (ref "U4") (pin "T4") (pinfunction "IO_L13N_T2_MRCC_34_T4") (pintype "bidirectional"))
    )
    (net (code "50") (name "/DDR3_ZQ") (class "Default")
      (node (ref "R36") (pin "2") (pinfunction "2_2") (pintype "passive"))
      (node (ref "U15") (pin "L8") (pinfunction "ZQ_L8") (pintype "input"))
    )
    (net (code "51") (name "/DDR_EN") (class "Default")
      (node (ref "U16") (pin "7") (pinfunction "S3_7") (pintype "input"))
      (node (ref "U16") (pin "9") (pinfunction "S5_9") (pintype "input"))
    )
    (net (code "52") (name "DDRVCC") (class "Default")
      (node (ref "C103") (pin "1") (pinfunction "1_1") (pintype "passive"))
      (node (ref "C106") (pin "1") (pinfunction "1_1") (pintype "passive"))
      (node (ref "R61") (pin "1") (pinfunction "1_1") (pintype "passive"))
      (node (ref "U16") (pin "1") (pinfunction "VDDQSNS_1") (pintype "input"))
    )
    (net (code "53") (name "DDRVCC_DD") (class "Default")
      (node (ref "C100") (pin "1") (pinfunction "1_1") (pintype "passive"))
      (node (ref "C101") (pin "1") (pinfunction "1_1") (pintype "passive"))
      (node (ref "C102") (pin "2") (pinfunction "2_2") (pintype "passive"))
      (node (ref "C92") (pin "1") (pinfunction "1_1") (pintype "passive"))
      (node (ref "C93") (pin "1") (pinfunction "1_1") (pintype "passive"))
      (node (ref "C94") (pin "1") (pinfunction "1_1") (pintype "passive"))
      (node (ref "C95") (pin "1") (pinfunction "1_1") (pintype "passive"))
      (node (ref "C96") (pin "1") (pinfunction "1_1") (pintype "passive"))
      (node (ref "C97") (pin "1") (pinfunction "1_1") (pintype "passive"))
      (node (ref "C98") (pin "1") (pinfunction "1_1") (pintype "passive"))
      (node (ref "C99") (pin "1") (pinfunction "1_1") (pintype "passive"))
      (node (ref "U15") (pin "B2") (pinfunction "VDD_B2") (pintype "power_in"))
      (node (ref "U15") (pin "D9") (pinfunction "VDD_D9") (pintype "power_in"))
      (node (ref "U15") (pin "G7") (pinfunction "VDD_G7") (pintype "power_in"))
      (node (ref "U15") (pin "K2") (pinfunction "VDD_K2") (pintype "power_in"))
      (node (ref "U15") (pin "K8") (pinfunction "VDD_K8") (pintype "power_in"))
      (node (ref "U15") (pin "N1") (pinfunction "VDD_N1") (pintype "power_in"))
      (node (ref "U15") (pin "N9") (pinfunction "VDD_N9") (pintype "power_in"))
      (node (ref "U15") (pin "R1") (pinfunction "VDD_R1") (pintype "power_in"))
      (node (ref "U15") (pin "R9") (pinfunction "VDD_R9") (pintype "power_in"))
    )
    (net (code "54") (name "DDRVCC_DQ") (class "Default")
      (node (ref "C118") (pin "1") (pinfunction "1_1") (pintype "passive"))
      (node (ref "C119") (pin "1") (pinfunction "1_1") (pintype "passive"))
      (node (ref "C120") (pin "1") (pinfunction "1_1") (pintype "passive"))
      (node (ref "C87") (pin "1") (pinfunction "1_1") (pintype "passive"))
      (node (ref "C88") (pin "1") (pinfunction "1_1") (pintype "passive"))
      (node (ref "C89") (pin "1") (pinfunction "1_1") (pintype "passive"))
      (node (ref "C90") (pin "1") (pinfunction "1_1") (pintype "passive"))
      (node (ref "C91") (pin "1") (pinfunction "1_1") (pintype "passive"))
      (node (ref "U15") (pin "A1") (pinfunction "VDDQ_A1") (pintype "power_in"))
      (node (ref "U15") (pin "A8") (pinfunction "VDDQ_A8") (pintype "power_in"))
      (node (ref "U15") (pin "C1") (pinfunction "VDDQ_C1") (pintype "power_in"))
      (node (ref "U15") (pin "C9") (pinfunction "VDDQ_C9") (pintype "power_in"))
      (node (ref "U15") (pin "D2") (pinfunction "VDDQ_D2") (pintype "power_in"))
      (node (ref "U15") (pin "E9") (pinfunction "VDDQ_E9") (pintype "power_in"))
      (node (ref "U15") (pin "F1") (pinfunction "VDDQ_F1") (pintype "power_in"))
      (node (ref "U15") (pin "H2") (pinfunction "VDDQ_H2") (pintype "power_in"))
      (node (ref "U15") (pin "H9") (pinfunction "VDDQ_H9") (pintype "power_in"))
    )
    (net (code "55") (name "DDRVREF") (class "Default")
      (node (ref "C103") (pin "2") (pinfunction "2_2") (pintype "passive"))
      (node (ref "C104") (pin "2") (pinfunction "2_2") (pintype "passive"))
      (node (ref "C105") (pin "1") (pinfunction "1_1") (pintype "passive"))
      (node (ref "C108") (pin "1") (pinfunction "1_1") (pintype "passive"))
      (node (ref "U15") (pin "H1") (pinfunction "VREFDQ_H1") (pintype "input"))
      (node (ref "U15") (pin "M8") (pinfunction "VREFCA_M8") (pintype "input"))
      (node (ref "U16") (pin "6") (pinfunction "VTTREF_6") (pintype "output"))
    )
    (net (code "56") (name "DDRVTT") (class "Default")
      (node (ref "C107") (pin "1") (pinfunction "1_1") (pintype "passive"))
      (node (ref "C111") (pin "2") (pinfunction "2_2") (pintype "passive"))
      (node (ref "C112") (pin "2") (pinfunction "2_2") (pintype "passive"))
      (node (ref "C113") (pin "2") (pinfunction "2_2") (pintype "passive"))
      (node (ref "C114") (pin "2") (pinfunction "2_2") (pintype "passive"))
      (node (ref "C115") (pin "2") (pinfunction "2_2") (pintype "passive"))
      (node (ref "C116") (pin "2") (pinfunction "2_2") (pintype "passive"))
      (node (ref "C117") (pin "2") (pinfunction "2_2") (pintype "passive"))
      (node (ref "R38") (pin "2") (pinfunction "2_2") (pintype "passive"))
      (node (ref "R39") (pin "2") (pinfunction "2_2") (pintype "passive"))
      (node (ref "R40") (pin "2") (pinfunction "2_2") (pintype "passive"))
      (node (ref "R41") (pin "2") (pinfunction "2_2") (pintype "passive"))
      (node (ref "R42") (pin "2") (pinfunction "2_2") (pintype "passive"))
      (node (ref "R43") (pin "2") (pinfunction "2_2") (pintype "passive"))
      (node (ref "R44") (pin "2") (pinfunction "2_2") (pintype "passive"))
      (node (ref "R45") (pin "2") (pinfunction "2_2") (pintype "passive"))
      (node (ref "R46") (pin "2") (pinfunction "2_2") (pintype "passive"))
      (node (ref "R47") (pin "2") (pinfunction "2_2") (pintype "passive"))
      (node (ref "R48") (pin "2") (pinfunction "2_2") (pintype "passive"))
      (node (ref "R49") (pin "2") (pinfunction "2_2") (pintype "passive"))
      (node (ref "R50") (pin "2") (pinfunction "2_2") (pintype "passive"))
      (node (ref "R51") (pin "2") (pinfunction "2_2") (pintype "passive"))
      (node (ref "R52") (pin "2") (pinfunction "2_2") (pintype "passive"))
      (node (ref "R53") (pin "2") (pinfunction "2_2") (pintype "passive"))
      (node (ref "R54") (pin "2") (pinfunction "2_2") (pintype "passive"))
      (node (ref "R55") (pin "2") (pinfunction "2_2") (pintype "passive"))
      (node (ref "R56") (pin "2") (pinfunction "2_2") (pintype "passive"))
      (node (ref "R57") (pin "2") (pinfunction "2_2") (pintype "passive"))
      (node (ref "R58") (pin "2") (pinfunction "2_2") (pintype "passive"))
      (node (ref "U16") (pin "3") (pinfunction "VTT_3") (pintype "power_in"))
      (node (ref "U16") (pin "5") (pinfunction "VTTSNS_5") (pintype "input"))
    )
    (net (code "57") (name "GND") (class "Default")
      (node (ref "C100") (pin "2") (pinfunction "2_2") (pintype "passive"))
      (node (ref "C101") (pin "2") (pinfunction "2_2") (pintype "passive"))
      (node (ref "C102") (pin "1") (pinfunction "1_1") (pintype "passive"))
      (node (ref "C104") (pin "1") (pinfunction "1_1") (pintype "passive"))
      (node (ref "C105") (pin "2") (pinfunction "2_2") (pintype "passive"))
      (node (ref "C107") (pin "2") (pinfunction "2_2") (pintype "passive"))
      (node (ref "C108") (pin "2") (pinfunction "2_2") (pintype "passive"))
      (node (ref "C109") (pin "2") (pinfunction "2_2") (pintype "passive"))
      (node (ref "C110") (pin "2") (pinfunction "2_2") (pintype "passive"))
      (node (ref "C111") (pin "1") (pinfunction "1_1") (pintype "passive"))
      (node (ref "C112") (pin "1") (pinfunction "1_1") (pintype "passive"))
      (node (ref "C113") (pin "1") (pinfunction "1_1") (pintype "passive"))
      (node (ref "C114") (pin "1") (pinfunction "1_1") (pintype "passive"))
      (node (ref "C115") (pin "1") (pinfunction "1_1") (pintype "passive"))
      (node (ref "C116") (pin "1") (pinfunction "1_1") (pintype "passive"))
      (node (ref "C117") (pin "1") (pinfunction "1_1") (pintype "passive"))
      (node (ref "C118") (pin "2") (pinfunction "2_2") (pintype "passive"))
      (node (ref "C119") (pin "2") (pinfunction "2_2") (pintype "passive"))
      (node (ref "C120") (pin "2") (pinfunction "2_2") (pintype "passive"))
      (node (ref "C87") (pin "2") (pinfunction "2_2") (pintype "passive"))
      (node (ref "C88") (pin "2") (pinfunction "2_2") (pintype "passive"))
      (node (ref "C89") (pin "2") (pinfunction "2_2") (pintype "passive"))
      (node (ref "C90") (pin "2") (pinfunction "2_2") (pintype "passive"))
      (node (ref "C91") (pin "2") (pinfunction "2_2") (pintype "passive"))
      (node (ref "C92") (pin "2") (pinfunction "2_2") (pintype "passive"))
      (node (ref "C93") (pin "2") (pinfunction "2_2") (pintype "passive"))
      (node (ref "C94") (pin "2") (pinfunction "2_2") (pintype "passive"))
      (node (ref "C95") (pin "2") (pinfunction "2_2") (pintype "passive"))
      (node (ref "C96") (pin "2") (pinfunction "2_2") (pintype "passive"))
      (node (ref "C97") (pin "2") (pinfunction "2_2") (pintype "passive"))
      (node (ref "C98") (pin "2") (pinfunction "2_2") (pintype "passive"))
      (node (ref "C99") (pin "2") (pinfunction "2_2") (pintype "passive"))
      (node (ref "R36") (pin "1") (pinfunction "1_1") (pintype "passive"))
      (node (ref "R37") (pin "1") (pinfunction "1_1") (pintype "passive"))
      (node (ref "U15") (pin "A9") (pinfunction "VSS_A9") (pintype "power_in"))
      (node (ref "U15") (pin "B1") (pinfunction "VSSQ_B1") (pintype "power_in"))
      (node (ref "U15") (pin "B3") (pinfunction "VSS_B3") (pintype "power_in"))
      (node (ref "U15") (pin "B9") (pinfunction "VSSQ_B9") (pintype "power_in"))
      (node (ref "U15") (pin "D1") (pinfunction "VSSQ_D1") (pintype "power_in"))
      (node (ref "U15") (pin "D8") (pinfunction "VSSQ_D8") (pintype "power_in"))
      (node (ref "U15") (pin "E1") (pinfunction "VSS_E1") (pintype "power_in"))
      (node (ref "U15") (pin "E2") (pinfunction "VSSQ_E2") (pintype "power_in"))
      (node (ref "U15") (pin "E8") (pinfunction "VSSQ_E8") (pintype "power_in"))
      (node (ref "U15") (pin "F9") (pinfunction "VSSQ_F9") (pintype "power_in"))
      (node (ref "U15") (pin "G1") (pinfunction "VSSQ_G1") (pintype "power_in"))
      (node (ref "U15") (pin "G8") (pinfunction "VSS_G8") (pintype "power_in"))
      (node (ref "U15") (pin "G9") (pinfunction "VSSQ_G9") (pintype "power_in"))
      (node (ref "U15") (pin "J2") (pinfunction "VSS_J2") (pintype "power_in"))
      (node (ref "U15") (pin "J8") (pinfunction "VSS_J8") (pintype "power_in"))
      (node (ref "U15") (pin "M1") (pinfunction "VSS_M1") (pintype "power_in"))
      (node (ref "U15") (pin "M9") (pinfunction "VSS_M9") (pintype "power_in"))
      (node (ref "U15") (pin "P1") (pinfunction "VSS_P1") (pintype "power_in"))
      (node (ref "U15") (pin "P9") (pinfunction "VSS_P9") (pintype "power_in"))
      (node (ref "U15") (pin "T1") (pinfunction "VSS_T1") (pintype "power_in"))
      (node (ref "U15") (pin "T9") (pinfunction "VSS_T9") (pintype "power_in"))
      (node (ref "U16") (pin "11") (pinfunction "EP_11") (pintype "power_in"))
      (node (ref "U16") (pin "4") (pinfunction "PGND_4") (pintype "power_in"))
      (node (ref "U16") (pin "8") (pinfunction "GND_8") (pintype "power_in"))
    )
    (net (code "58") (name "Net-(C106-Pad2)") (class "Default")
      (node (ref "C106") (pin "2") (pinfunction "2_2") (pintype "passive"))
      (node (ref "R59") (pin "1") (pinfunction "1_1") (pintype "passive"))
      (node (ref "R60") (pin "1") (pinfunction "1_1") (pintype "passive"))
    )
    (net (code "59") (name "Net-(U16-VLDOIN)") (class "Default")
      (node (ref "C109") (pin "1") (pinfunction "1_1") (pintype "passive"))
      (node (ref "R61") (pin "2") (pinfunction "2_2") (pintype "passive"))
      (node (ref "U16") (pin "2") (pinfunction "VLDOIN_2") (pintype "power_in"))
    )
    (net (code "60") (name "unconnected-(U4D-IO_L6N_T0_VREF_34-PadV3)") (class "Default")
      (node (ref "U4") (pin "V3") (pinfunction "IO_L6N_T0_VREF_34_V3") (pintype "bidirectional+no_connect"))
    )
    (net (code "61") (name "unconnected-(U4D-IO_L12N_T1_MRCC_34-PadW4)") (class "Default")
      (node (ref "U4") (pin "W4") (pinfunction "IO_L12N_T1_MRCC_34_W4") (pintype "bidirectional+no_connect"))
    )
    (net (code "62") (name "unconnected-(U15C-NC-PadJ1)") (class "Default")
      (node (ref "U15") (pin "J1") (pinfunction "NC_J1") (pintype "passive"))
    )
    (net (code "63") (name "unconnected-(U15C-NC-PadJ9)") (class "Default")
      (node (ref "U15") (pin "J9") (pinfunction "NC_J9") (pintype "passive"))
    )
    (net (code "64") (name "unconnected-(U15C-NC-PadL1)") (class "Default")
      (node (ref "U15") (pin "L1") (pinfunction "NC_L1") (pintype "passive"))
    )
    (net (code "65") (name "unconnected-(U15C-NC-PadL9)") (class "Default")
      (node (ref "U15") (pin "L9") (pinfunction "NC_L9") (pintype "passive"))
    )
    (net (code "66") (name "unconnected-(U15C-NC-PadM7)") (class "Default")
      (node (ref "U15") (pin "M7") (pinfunction "NC_M7") (pintype "passive"))
    )
    (net (code "67") (name "unconnected-(U15C-NC-PadT7)") (class "Default")
      (node (ref "U15") (pin "T7") (pinfunction "NC_T7") (pintype "passive"))
    )
  )
)
